# IMX8_PHY.net
KiCad netlist of a schematic drawn in Altium Designer
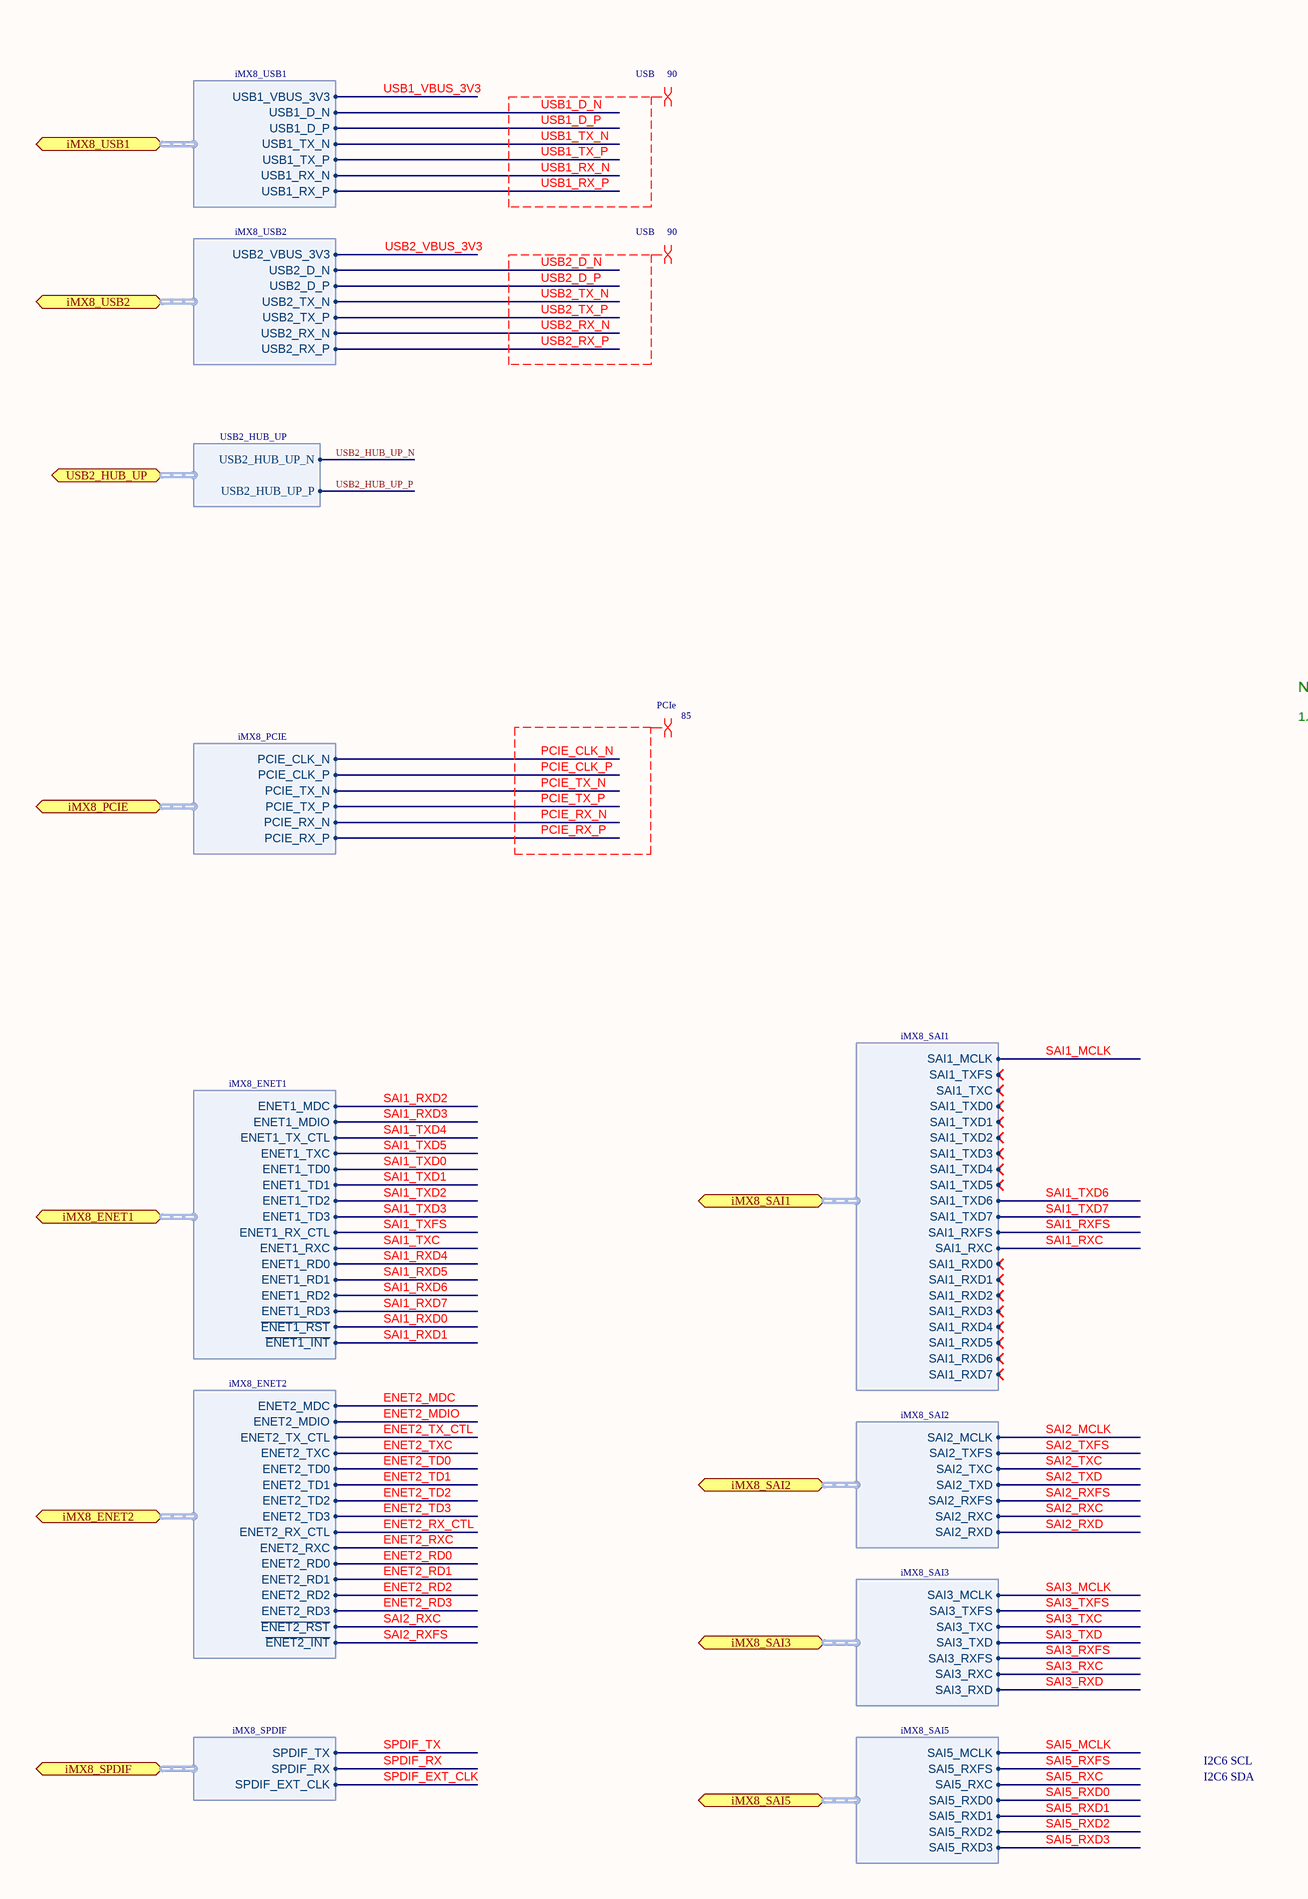
[diagram p0: IMX8_PHY.SchDoc, left]
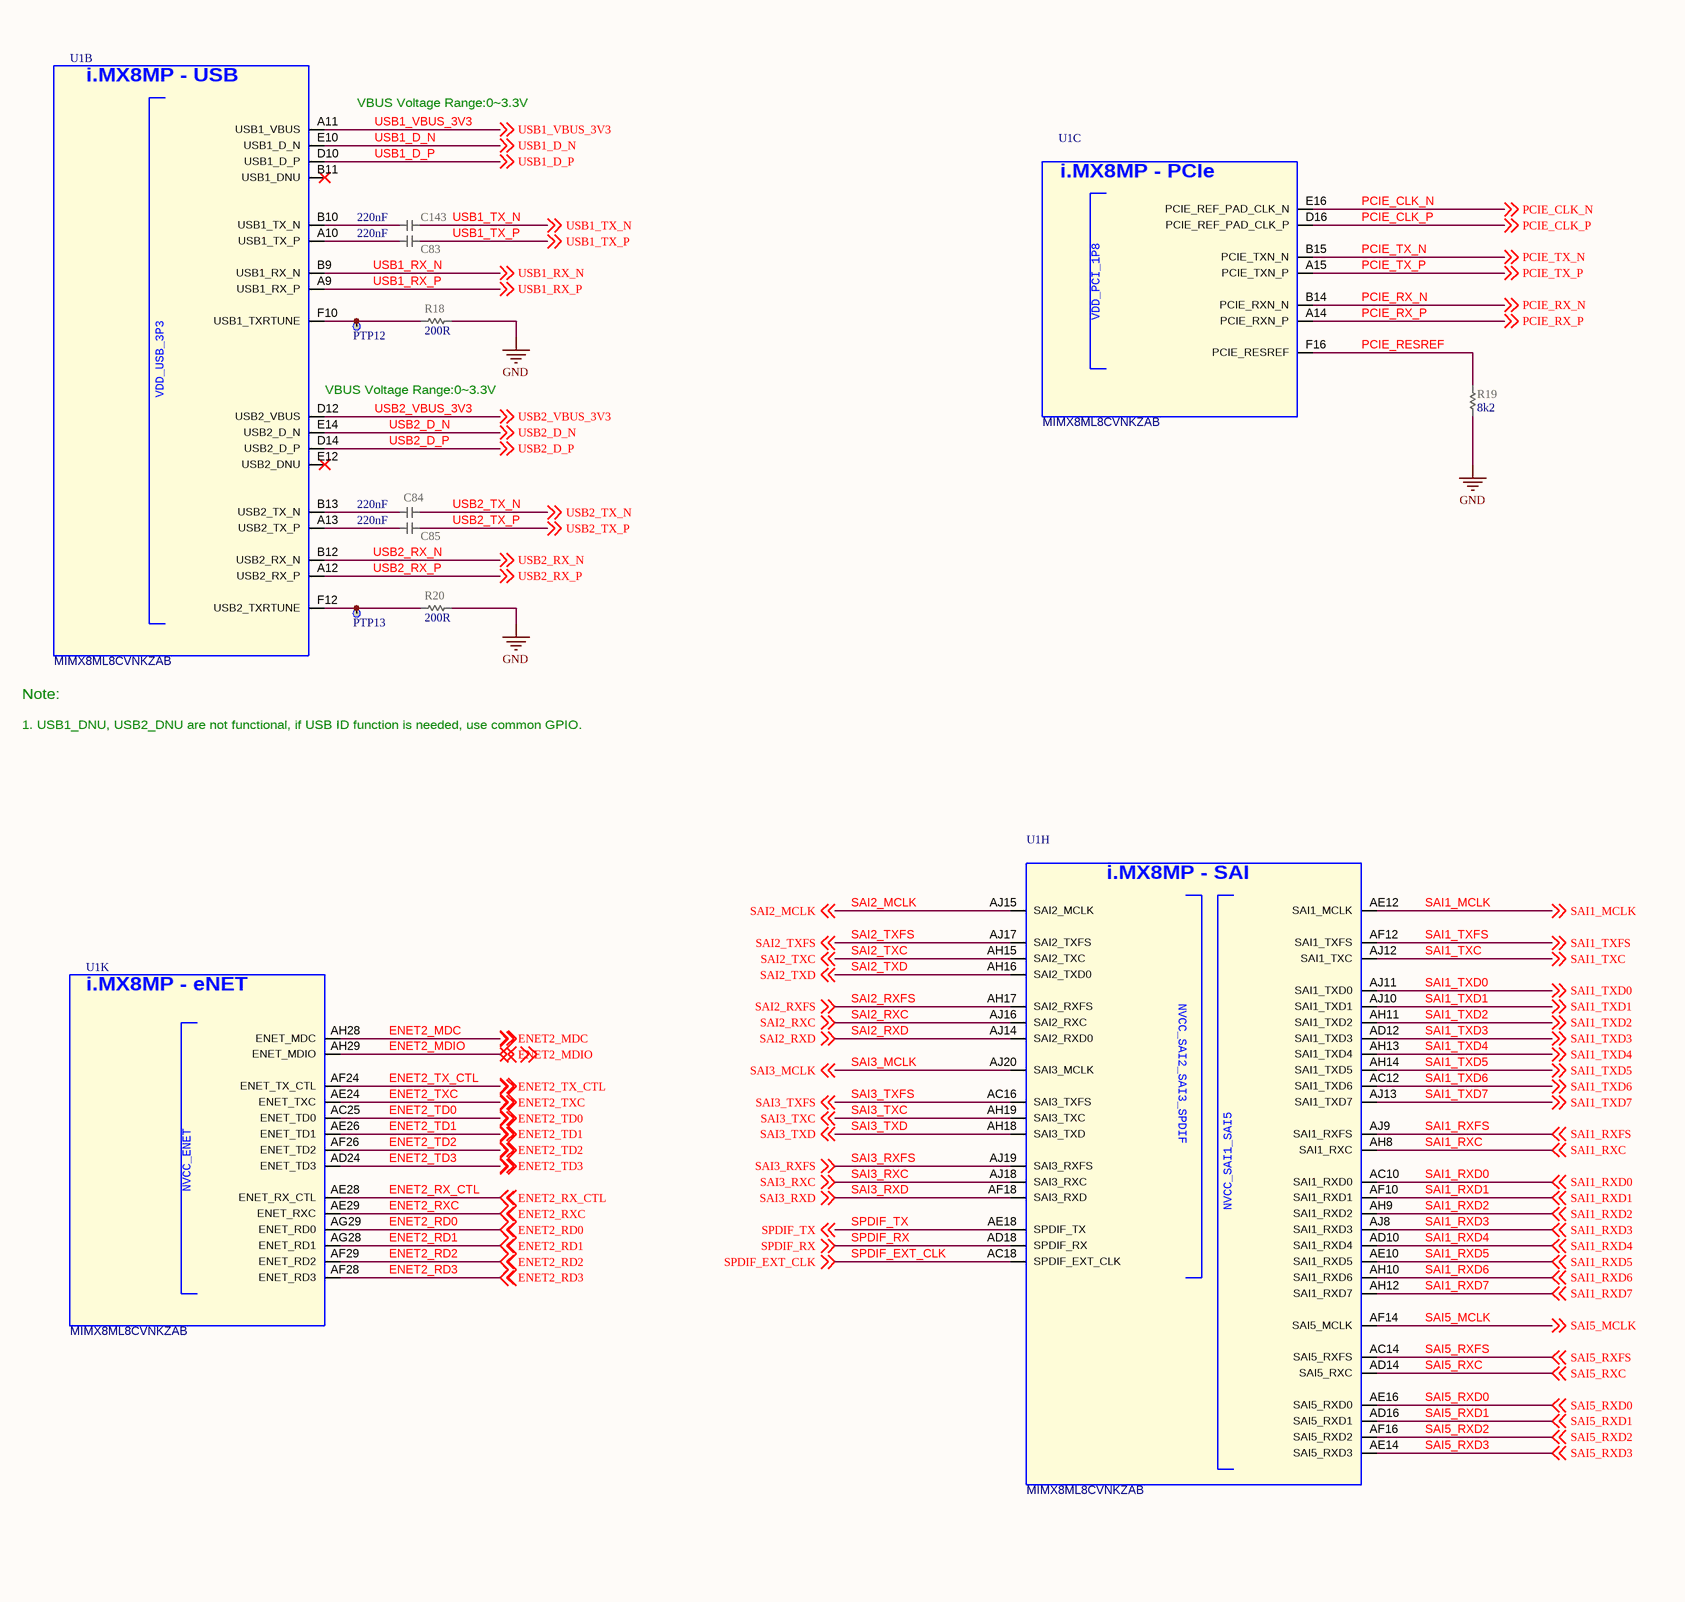
[diagram p1: IMX8_PHY.SchDoc, right]

(export (version "E")
  (design (tool "Eeschema 10.0.6"))
  (components
    (comp (ref "C83")
      (value "220nF")
      (footprint "CAP_0201_UN1Q")
      (description "CAP")
      (fields (field (name "PART NUMBER") "GRM033C81A224KE01D") (field (name "MANUFACTURER") "Murata"))
      (libsource (lib "robo_cam") (part "CMP-001-000889-11"))
    )
    (comp (ref "C84")
      (value "220nF")
      (footprint "CAP_0201_UN1Q")
      (description "CAP")
      (fields (field (name "PART NUMBER") "GRM033C81A224KE01D") (field (name "MANUFACTURER") "Murata"))
      (libsource (lib "robo_cam") (part "CMP-001-000889-11"))
    )
    (comp (ref "C85")
      (value "220nF")
      (footprint "CAP_0201_UN1Q")
      (description "CAP")
      (fields (field (name "PART NUMBER") "GRM033C81A224KE01D") (field (name "MANUFACTURER") "Murata"))
      (libsource (lib "robo_cam") (part "CMP-001-000889-11"))
    )
    (comp (ref "C143")
      (value "220nF")
      (footprint "CAP_0201_UN1Q")
      (description "CAP")
      (fields (field (name "PART NUMBER") "GRM033C81A224KE01D") (field (name "MANUFACTURER") "Murata"))
      (libsource (lib "robo_cam") (part "CMP-001-000889-11"))
    )
    (comp (ref "PTP12")
      (value "PTP_0.4mm")
      (footprint "PTP_0.4mm")
      (description "Production Testpoint 0.4mm. Flying probe. Use 1mm pitch.")
      (fields (field (name "PART NUMBER") "PTP 0.4mm"))
      (libsource (lib "TII_WS") (part "PTP 0.4mm"))
    )
    (comp (ref "PTP13")
      (value "PTP_0.4mm")
      (footprint "PTP_0.4mm")
      (description "Production Testpoint 0.4mm. Flying probe. Use 1mm pitch.")
      (fields (field (name "PART NUMBER") "PTP 0.4mm"))
      (libsource (lib "TII_WS") (part "PTP 0.4mm"))
    )
    (comp (ref "R18")
      (value "200R")
      (footprint "RES_0201_UN1Q")
      (description "RES")
      (fields (field (name "TOLERANCE") "1%") (field (name "PART NUMBER") "CRCW0201200RFNED"))
      (libsource (lib "TII_WS") (part "RES_Common"))
    )
    (comp (ref "R19")
      (value "8k2")
      (footprint "RES_0201_UN1Q")
      (description "RES")
      (fields (field (name "TOLERANCE") "1%") (field (name "PART NUMBER") "ERJ1GNF8201C"))
      (libsource (lib "CM5_library") (part "CMP-001-001255-9"))
    )
    (comp (ref "R20")
      (value "200R")
      (footprint "RES_0201_UN1Q")
      (description "RES")
      (fields (field (name "TOLERANCE") "1%") (field (name "PART NUMBER") "CRCW0201200RFNED"))
      (libsource (lib "TII_WS") (part "RES_Common"))
    )
    (comp (ref "U1")
      (value "MIMX8ML8CVNKZAB")
      (footprint "BGA548C50P29X29_1500X1500X148")
      (description "CPU QUAD CORTEX A53+M4 1.6GHZ BGA548 Industrial")
      (fields
        (field (name "MANUFACTURER") "NXP Semiconductors")
        (field (name "PART NUMBER") "MIMX8ML8CVNKZAB")
        (field (name "SOURCE") "UUDET_KOMPONENTIT.SchLib")
      )
      (libsource (lib "robo_cam") (part "CMP-001-000983-8"))
    )
  )
  (nets
    (net (code "12") (name "/PCIE_RESREF") (class "Default")
      (node (ref "R19") (pin "2") (pinfunction "2_2") (pintype "passive"))
      (node (ref "U1") (pin "F16") (pinfunction "PCIE_RESREF_F16") (pintype "passive"))
    )
    (net (code "26") (name "ENET2_MDC") (class "Default")
      (node (ref "U1") (pin "AH28") (pinfunction "ENET_MDC_AH28") (pintype "passive"))
    )
    (net (code "27") (name "ENET2_MDIO") (class "Default")
      (node (ref "U1") (pin "AH29") (pinfunction "ENET_MDIO_AH29") (pintype "passive"))
    )
    (net (code "28") (name "ENET2_RD0") (class "Default")
      (node (ref "U1") (pin "AG29") (pinfunction "ENET_RD0_AG29") (pintype "passive"))
    )
    (net (code "29") (name "ENET2_RD1") (class "Default")
      (node (ref "U1") (pin "AG28") (pinfunction "ENET_RD1_AG28") (pintype "passive"))
    )
    (net (code "30") (name "ENET2_RD2") (class "Default")
      (node (ref "U1") (pin "AF29") (pinfunction "ENET_RD2_AF29") (pintype "passive"))
    )
    (net (code "31") (name "ENET2_RD3") (class "Default")
      (node (ref "U1") (pin "AF28") (pinfunction "ENET_RD3_AF28") (pintype "passive"))
    )
    (net (code "32") (name "ENET2_RXC") (class "Default")
      (node (ref "U1") (pin "AE29") (pinfunction "ENET_RXC_AE29") (pintype "passive"))
    )
    (net (code "33") (name "ENET2_RX_CTL") (class "Default")
      (node (ref "U1") (pin "AE28") (pinfunction "ENET_RX_CTL_AE28") (pintype "passive"))
    )
    (net (code "34") (name "ENET2_TD0") (class "Default")
      (node (ref "U1") (pin "AC25") (pinfunction "ENET_TD0_AC25") (pintype "passive"))
    )
    (net (code "35") (name "ENET2_TD1") (class "Default")
      (node (ref "U1") (pin "AE26") (pinfunction "ENET_TD1_AE26") (pintype "passive"))
    )
    (net (code "36") (name "ENET2_TD2") (class "Default")
      (node (ref "U1") (pin "AF26") (pinfunction "ENET_TD2_AF26") (pintype "passive"))
    )
    (net (code "37") (name "ENET2_TD3") (class "Default")
      (node (ref "U1") (pin "AD24") (pinfunction "ENET_TD3_AD24") (pintype "passive"))
    )
    (net (code "38") (name "ENET2_TXC") (class "Default")
      (node (ref "U1") (pin "AE24") (pinfunction "ENET_TXC_AE24") (pintype "passive"))
    )
    (net (code "39") (name "ENET2_TX_CTL") (class "Default")
      (node (ref "U1") (pin "AF24") (pinfunction "ENET_TX_CTL_AF24") (pintype "passive"))
    )
    (net (code "40") (name "GND") (class "Default")
      (node (ref "R18") (pin "1") (pinfunction "1_1") (pintype "passive"))
      (node (ref "R19") (pin "1") (pinfunction "1_1") (pintype "passive"))
      (node (ref "R20") (pin "1") (pinfunction "1_1") (pintype "passive"))
    )
    (net (code "41") (name "Net-(PTP12-TP)") (class "Default")
      (node (ref "PTP12") (pin "1") (pinfunction "TP_1") (pintype "passive"))
      (node (ref "R18") (pin "2") (pinfunction "2_2") (pintype "passive"))
      (node (ref "U1") (pin "F10") (pinfunction "USB1_TXRTUNE_F10") (pintype "passive"))
    )
    (net (code "42") (name "Net-(PTP13-TP)") (class "Default")
      (node (ref "PTP13") (pin "1") (pinfunction "TP_1") (pintype "passive"))
      (node (ref "R20") (pin "2") (pinfunction "2_2") (pintype "passive"))
      (node (ref "U1") (pin "F12") (pinfunction "USB2_TXRTUNE_F12") (pintype "passive"))
    )
    (net (code "43") (name "Net-(U1B-USB1_TX_N)") (class "Default")
      (node (ref "C143") (pin "1") (pinfunction "1_1") (pintype "passive"))
      (node (ref "U1") (pin "B10") (pinfunction "USB1_TX_N_B10") (pintype "passive"))
    )
    (net (code "44") (name "Net-(U1B-USB1_TX_P)") (class "Default")
      (node (ref "C83") (pin "2") (pinfunction "2_2") (pintype "passive"))
      (node (ref "U1") (pin "A10") (pinfunction "USB1_TX_P_A10") (pintype "passive"))
    )
    (net (code "45") (name "Net-(U1B-USB2_TX_N)") (class "Default")
      (node (ref "C84") (pin "1") (pinfunction "1_1") (pintype "passive"))
      (node (ref "U1") (pin "B13") (pinfunction "USB2_TX_N_B13") (pintype "passive"))
    )
    (net (code "46") (name "Net-(U1B-USB2_TX_P)") (class "Default")
      (node (ref "C85") (pin "1") (pinfunction "1_1") (pintype "passive"))
      (node (ref "U1") (pin "A13") (pinfunction "USB2_TX_P_A13") (pintype "passive"))
    )
    (net (code "47") (name "PCIE_CLK_N") (class "Default")
      (node (ref "U1") (pin "E16") (pinfunction "PCIE_REF_PAD_CLK_N_E16") (pintype "passive"))
    )
    (net (code "48") (name "PCIE_CLK_P") (class "Default")
      (node (ref "U1") (pin "D16") (pinfunction "PCIE_REF_PAD_CLK_P_D16") (pintype "passive"))
    )
    (net (code "49") (name "PCIE_RX_N") (class "Default")
      (node (ref "U1") (pin "B14") (pinfunction "PCIE_RXN_N_B14") (pintype "passive"))
    )
    (net (code "50") (name "PCIE_RX_P") (class "Default")
      (node (ref "U1") (pin "A14") (pinfunction "PCIE_RXN_P_A14") (pintype "passive"))
    )
    (net (code "51") (name "PCIE_TX_N") (class "Default")
      (node (ref "U1") (pin "B15") (pinfunction "PCIE_TXN_N_B15") (pintype "passive"))
    )
    (net (code "52") (name "PCIE_TX_P") (class "Default")
      (node (ref "U1") (pin "A15") (pinfunction "PCIE_TXN_P_A15") (pintype "passive"))
    )
    (net (code "53") (name "SAI1_MCLK") (class "Default")
      (node (ref "U1") (pin "AE12") (pinfunction "SAI1_MCLK_AE12") (pintype "passive"))
    )
    (net (code "54") (name "SAI1_RXC") (class "Default")
      (node (ref "U1") (pin "AH8") (pinfunction "SAI1_RXC_AH8") (pintype "passive"))
    )
    (net (code "55") (name "SAI1_RXD0") (class "Default")
      (node (ref "U1") (pin "AC10") (pinfunction "SAI1_RXD0_AC10") (pintype "passive"))
    )
    (net (code "56") (name "SAI1_RXD1") (class "Default")
      (node (ref "U1") (pin "AF10") (pinfunction "SAI1_RXD1_AF10") (pintype "passive"))
    )
    (net (code "57") (name "SAI1_RXD2") (class "Default")
      (node (ref "U1") (pin "AH9") (pinfunction "SAI1_RXD2_AH9") (pintype "passive"))
    )
    (net (code "58") (name "SAI1_RXD3") (class "Default")
      (node (ref "U1") (pin "AJ8") (pinfunction "SAI1_RXD3_AJ8") (pintype "passive"))
    )
    (net (code "59") (name "SAI1_RXD4") (class "Default")
      (node (ref "U1") (pin "AD10") (pinfunction "SAI1_RXD4_AD10") (pintype "passive"))
    )
    (net (code "60") (name "SAI1_RXD5") (class "Default")
      (node (ref "U1") (pin "AE10") (pinfunction "SAI1_RXD5_AE10") (pintype "passive"))
    )
    (net (code "61") (name "SAI1_RXD6") (class "Default")
      (node (ref "U1") (pin "AH10") (pinfunction "SAI1_RXD6_AH10") (pintype "passive"))
    )
    (net (code "62") (name "SAI1_RXD7") (class "Default")
      (node (ref "U1") (pin "AH12") (pinfunction "SAI1_RXD7_AH12") (pintype "passive"))
    )
    (net (code "63") (name "SAI1_RXFS") (class "Default")
      (node (ref "U1") (pin "AJ9") (pinfunction "SAI1_RXFS_AJ9") (pintype "passive"))
    )
    (net (code "64") (name "SAI1_TXC") (class "Default")
      (node (ref "U1") (pin "AJ12") (pinfunction "SAI1_TXC_AJ12") (pintype "passive"))
    )
    (net (code "65") (name "SAI1_TXD0") (class "Default")
      (node (ref "U1") (pin "AJ11") (pinfunction "SAI1_TXD0_AJ11") (pintype "passive"))
    )
    (net (code "66") (name "SAI1_TXD1") (class "Default")
      (node (ref "U1") (pin "AJ10") (pinfunction "SAI1_TXD1_AJ10") (pintype "passive"))
    )
    (net (code "67") (name "SAI1_TXD2") (class "Default")
      (node (ref "U1") (pin "AH11") (pinfunction "SAI1_TXD2_AH11") (pintype "passive"))
    )
    (net (code "68") (name "SAI1_TXD3") (class "Default")
      (node (ref "U1") (pin "AD12") (pinfunction "SAI1_TXD3_AD12") (pintype "passive"))
    )
    (net (code "69") (name "SAI1_TXD4") (class "Default")
      (node (ref "U1") (pin "AH13") (pinfunction "SAI1_TXD4_AH13") (pintype "passive"))
    )
    (net (code "70") (name "SAI1_TXD5") (class "Default")
      (node (ref "U1") (pin "AH14") (pinfunction "SAI1_TXD5_AH14") (pintype "passive"))
    )
    (net (code "71") (name "SAI1_TXD6") (class "Default")
      (node (ref "U1") (pin "AC12") (pinfunction "SAI1_TXD6_AC12") (pintype "passive"))
    )
    (net (code "72") (name "SAI1_TXD7") (class "Default")
      (node (ref "U1") (pin "AJ13") (pinfunction "SAI1_TXD7_AJ13") (pintype "passive"))
    )
    (net (code "73") (name "SAI1_TXFS") (class "Default")
      (node (ref "U1") (pin "AF12") (pinfunction "SAI1_TXFS_AF12") (pintype "passive"))
    )
    (net (code "74") (name "SAI2_MCLK") (class "Default")
      (node (ref "U1") (pin "AJ15") (pinfunction "SAI2_MCLK_AJ15") (pintype "passive"))
    )
    (net (code "75") (name "SAI2_RXC") (class "Default")
      (node (ref "U1") (pin "AJ16") (pinfunction "SAI2_RXC_AJ16") (pintype "passive"))
    )
    (net (code "76") (name "SAI2_RXD") (class "Default")
      (node (ref "U1") (pin "AJ14") (pinfunction "SAI2_RXD0_AJ14") (pintype "passive"))
    )
    (net (code "77") (name "SAI2_RXFS") (class "Default")
      (node (ref "U1") (pin "AH17") (pinfunction "SAI2_RXFS_AH17") (pintype "passive"))
    )
    (net (code "78") (name "SAI2_TXC") (class "Default")
      (node (ref "U1") (pin "AH15") (pinfunction "SAI2_TXC_AH15") (pintype "passive"))
    )
    (net (code "79") (name "SAI2_TXD") (class "Default")
      (node (ref "U1") (pin "AH16") (pinfunction "SAI2_TXD0_AH16") (pintype "passive"))
    )
    (net (code "80") (name "SAI2_TXFS") (class "Default")
      (node (ref "U1") (pin "AJ17") (pinfunction "SAI2_TXFS_AJ17") (pintype "passive"))
    )
    (net (code "81") (name "SAI3_MCLK") (class "Default")
      (node (ref "U1") (pin "AJ20") (pinfunction "SAI3_MCLK_AJ20") (pintype "passive"))
    )
    (net (code "82") (name "SAI3_RXC") (class "Default")
      (node (ref "U1") (pin "AJ18") (pinfunction "SAI3_RXC_AJ18") (pintype "passive"))
    )
    (net (code "83") (name "SAI3_RXD") (class "Default")
      (node (ref "U1") (pin "AF18") (pinfunction "SAI3_RXD_AF18") (pintype "passive"))
    )
    (net (code "84") (name "SAI3_RXFS") (class "Default")
      (node (ref "U1") (pin "AJ19") (pinfunction "SAI3_RXFS_AJ19") (pintype "passive"))
    )
    (net (code "85") (name "SAI3_TXC") (class "Default")
      (node (ref "U1") (pin "AH19") (pinfunction "SAI3_TXC_AH19") (pintype "passive"))
    )
    (net (code "86") (name "SAI3_TXD") (class "Default")
      (node (ref "U1") (pin "AH18") (pinfunction "SAI3_TXD_AH18") (pintype "passive"))
    )
    (net (code "87") (name "SAI3_TXFS") (class "Default")
      (node (ref "U1") (pin "AC16") (pinfunction "SAI3_TXFS_AC16") (pintype "passive"))
    )
    (net (code "88") (name "SAI5_MCLK") (class "Default")
      (node (ref "U1") (pin "AF14") (pinfunction "SAI5_MCLK_AF14") (pintype "passive"))
    )
    (net (code "89") (name "SAI5_RXC") (class "Default")
      (node (ref "U1") (pin "AD14") (pinfunction "SAI5_RXC_AD14") (pintype "passive"))
    )
    (net (code "90") (name "SAI5_RXD0") (class "Default")
      (node (ref "U1") (pin "AE16") (pinfunction "SAI5_RXD0_AE16") (pintype "passive"))
    )
    (net (code "91") (name "SAI5_RXD1") (class "Default")
      (node (ref "U1") (pin "AD16") (pinfunction "SAI5_RXD1_AD16") (pintype "passive"))
    )
    (net (code "92") (name "SAI5_RXD2") (class "Default")
      (node (ref "U1") (pin "AF16") (pinfunction "SAI5_RXD2_AF16") (pintype "passive"))
    )
    (net (code "93") (name "SAI5_RXD3") (class "Default")
      (node (ref "U1") (pin "AE14") (pinfunction "SAI5_RXD3_AE14") (pintype "passive"))
    )
    (net (code "94") (name "SAI5_RXFS") (class "Default")
      (node (ref "U1") (pin "AC14") (pinfunction "SAI5_RXFS_AC14") (pintype "passive"))
    )
    (net (code "95") (name "SPDIF_EXT_CLK") (class "Default")
      (node (ref "U1") (pin "AC18") (pinfunction "SPDIF_EXT_CLK_AC18") (pintype "passive"))
    )
    (net (code "96") (name "SPDIF_RX") (class "Default")
      (node (ref "U1") (pin "AD18") (pinfunction "SPDIF_RX_AD18") (pintype "passive"))
    )
    (net (code "97") (name "SPDIF_TX") (class "Default")
      (node (ref "U1") (pin "AE18") (pinfunction "SPDIF_TX_AE18") (pintype "passive"))
    )
    (net (code "98") (name "USB1_D_N") (class "Default")
      (node (ref "U1") (pin "E10") (pinfunction "USB1_D_N_E10") (pintype "passive"))
    )
    (net (code "99") (name "USB1_D_P") (class "Default")
      (node (ref "U1") (pin "D10") (pinfunction "USB1_D_P_D10") (pintype "passive"))
    )
    (net (code "100") (name "USB1_RX_N") (class "Default")
      (node (ref "U1") (pin "B9") (pinfunction "USB1_RX_N_B9") (pintype "passive"))
    )
    (net (code "101") (name "USB1_RX_P") (class "Default")
      (node (ref "U1") (pin "A9") (pinfunction "USB1_RX_P_A9") (pintype "passive"))
    )
    (net (code "102") (name "USB1_TX_N") (class "Default")
      (node (ref "C143") (pin "2") (pinfunction "2_2") (pintype "passive"))
    )
    (net (code "103") (name "USB1_TX_P") (class "Default")
      (node (ref "C83") (pin "1") (pinfunction "1_1") (pintype "passive"))
    )
    (net (code "104") (name "USB1_VBUS_3V3") (class "Default")
      (node (ref "U1") (pin "A11") (pinfunction "USB1_VBUS_A11") (pintype "passive"))
    )
    (net (code "105") (name "USB2_D_N") (class "Default")
      (node (ref "U1") (pin "E14") (pinfunction "USB2_D_N_E14") (pintype "passive"))
    )
    (net (code "106") (name "USB2_D_P") (class "Default")
      (node (ref "U1") (pin "D14") (pinfunction "USB2_D_P_D14") (pintype "passive"))
    )
    (net (code "107") (name "USB2_RX_N") (class "Default")
      (node (ref "U1") (pin "B12") (pinfunction "USB2_RX_N_B12") (pintype "passive"))
    )
    (net (code "108") (name "USB2_RX_P") (class "Default")
      (node (ref "U1") (pin "A12") (pinfunction "USB2_RX_P_A12") (pintype "passive"))
    )
    (net (code "109") (name "USB2_TX_N") (class "Default")
      (node (ref "C84") (pin "2") (pinfunction "2_2") (pintype "passive"))
    )
    (net (code "110") (name "USB2_TX_P") (class "Default")
      (node (ref "C85") (pin "2") (pinfunction "2_2") (pintype "passive"))
    )
    (net (code "111") (name "USB2_VBUS_3V3") (class "Default")
      (node (ref "U1") (pin "D12") (pinfunction "USB2_VBUS_D12") (pintype "passive"))
    )
    (net (code "112") (name "unconnected-(U1B-USB1_DNU-PadB11)") (class "Default")
      (node (ref "U1") (pin "B11") (pinfunction "USB1_DNU_B11") (pintype "passive+no_connect"))
    )
    (net (code "113") (name "unconnected-(U1B-USB2_DNU-PadE12)") (class "Default")
      (node (ref "U1") (pin "E12") (pinfunction "USB2_DNU_E12") (pintype "passive+no_connect"))
    )
  )
)
